# Power_Board.net
KiCad netlist of a schematic drawn in Altium Designer
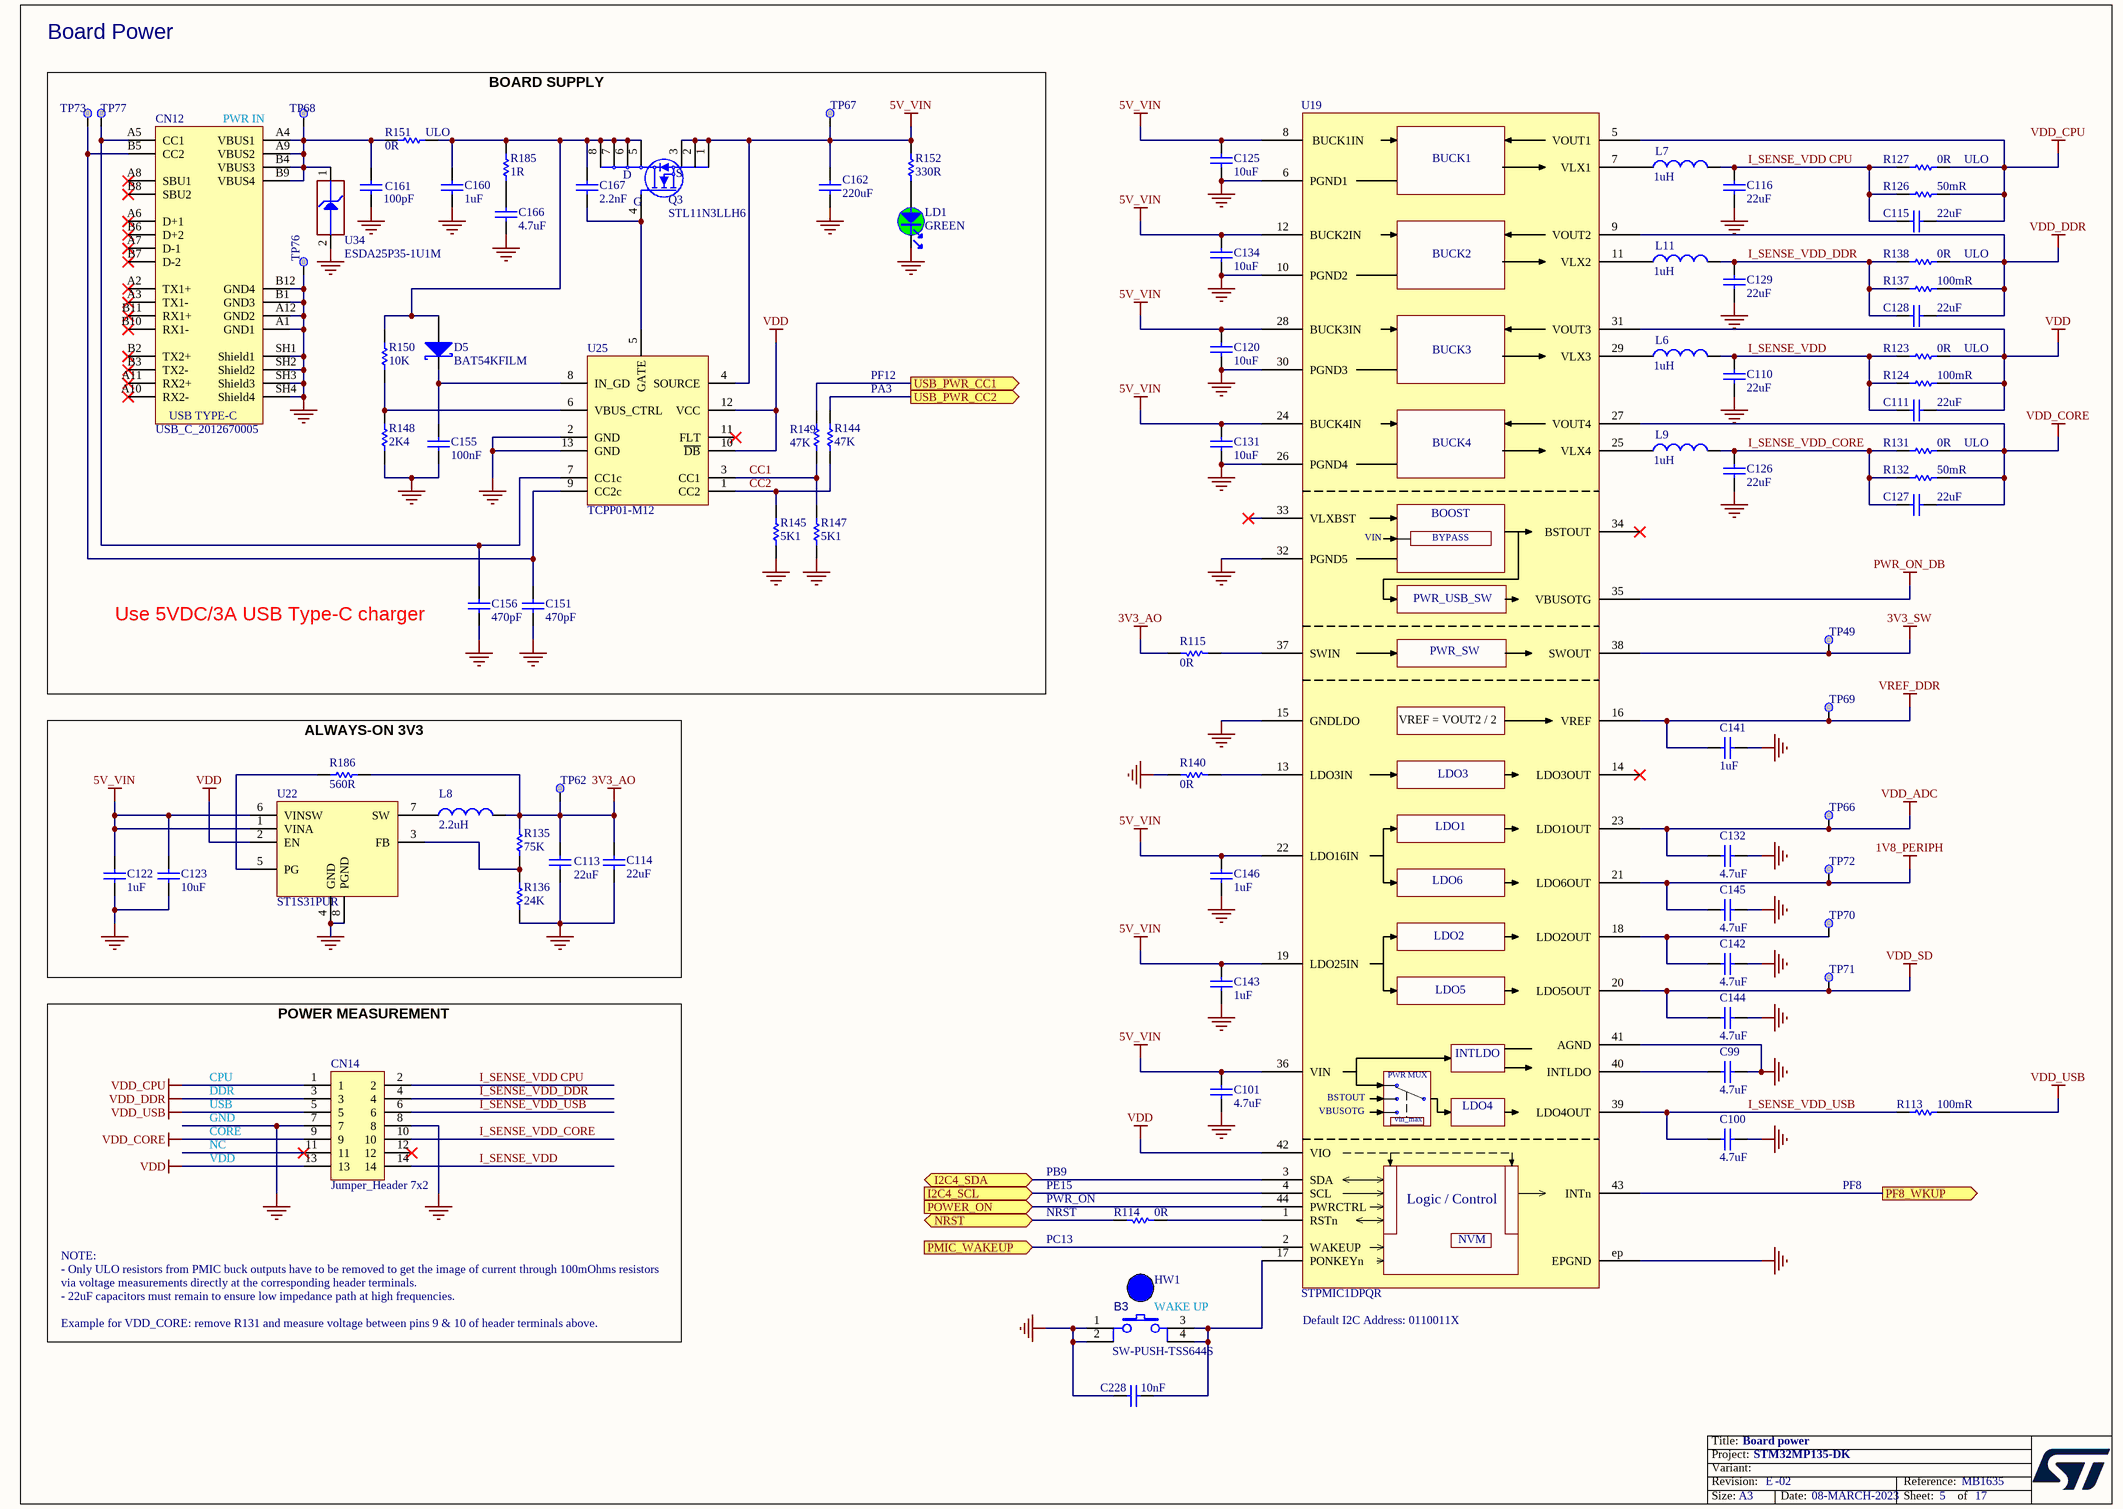
[diagram p0: Power_Board.SchDoc]

(export (version "E")
  (design (tool "Eeschema 10.0.6"))
  (components
    (comp (ref "B3")
      (value "SW-PUSH-TSS644S")
      (footprint "SWI_KNITTER_TSS644S")
      (description "Push Button, NO, 0.05A, 12V, 2.6N, SMD, 9.0x6.2mm, T=7.3mm, changeable caps KTSC-6xx")
      (fields
        (field (name "INTERNAL_PART_NUMBER") "MCD-02417")
        (field (name "MANUFACTURER_PART_NUMBER") "TSS644S")
      )
      (libsource (lib "MCD_PARTS_database") (part "SW_PUSH_SMD"))
    )
    (comp (ref "C99")
      (value "4.7uF")
      (footprint "C0402")
      (description "Capacitor, MLCC, 4.7uF, 6V3, X5R, +/-20%, 0402, T=0.5mm")
      (fields
        (field (name "INTERNAL_PART_NUMBER") "MCD-01356")
        (field (name "MANUFACTURER_PART_NUMBER") "GRM155R60J475ME47")
      )
      (libsource (lib "MCD_PARTS_database") (part "Capacitor"))
    )
    (comp (ref "C100")
      (value "4.7uF")
      (footprint "C0402")
      (description "Capacitor, MLCC, 4.7uF, 6V3, X5R, +/-20%, 0402, T=0.5mm")
      (fields
        (field (name "INTERNAL_PART_NUMBER") "MCD-01356")
        (field (name "MANUFACTURER_PART_NUMBER") "GRM155R60J475ME47")
      )
      (libsource (lib "MCD_PARTS_database") (part "Capacitor"))
    )
    (comp (ref "C101")
      (value "4.7uF")
      (footprint "C0402")
      (description "Capacitor, MLCC, 4.7uF, 6V3, X5R, +/-20%, 0402, T=0.5mm")
      (fields
        (field (name "INTERNAL_PART_NUMBER") "MCD-01356")
        (field (name "MANUFACTURER_PART_NUMBER") "GRM155R60J475ME47")
      )
      (libsource (lib "MCD_PARTS_database") (part "Capacitor"))
    )
    (comp (ref "C110")
      (value "22uF")
      (footprint "C0603")
      (description "Capacitor, MLCC, 22uF, 6V3, X5R, +/-20%, 0603, T=0.8mm")
      (fields
        (field (name "INTERNAL_PART_NUMBER") "MCD-00100")
        (field (name "MANUFACTURER_PART_NUMBER") "GRM188R60J226MEA0J")
      )
      (libsource (lib "MCD_PARTS_database") (part "Capacitor"))
    )
    (comp (ref "C111")
      (value "22uF")
      (footprint "C0603")
      (description "Capacitor, MLCC, 22uF, 6V3, X5R, +/-20%, 0603, T=0.8mm")
      (fields (field (name "INTERNAL_PART_NUMBER") "MCD-00100") (field (name "MANUFACTURER") "MURATA"))
      (libsource (lib "MCD_PARTS_database") (part "Capacitor"))
    )
    (comp (ref "C113")
      (value "22uF")
      (footprint "C0603")
      (description "Capacitor, MLCC, 22uF, 6V3, X5R, +/-20%, 0603, T=0.8mm")
      (fields (field (name "INTERNAL_PART_NUMBER") "MCD-00100") (field (name "MANUFACTURER") "MURATA"))
      (libsource (lib "MCD_PARTS_database") (part "Capacitor"))
    )
    (comp (ref "C114")
      (value "22uF")
      (footprint "C0603")
      (description "Capacitor, MLCC, 22uF, 6V3, X5R, +/-20%, 0603, T=0.8mm")
      (fields (field (name "INTERNAL_PART_NUMBER") "MCD-00100") (field (name "MANUFACTURER") "MURATA"))
      (libsource (lib "MCD_PARTS_database") (part "Capacitor"))
    )
    (comp (ref "C115")
      (value "22uF")
      (footprint "C0603")
      (description "Capacitor, MLCC, 22uF, 6V3, X5R, +/-20%, 0603, T=0.8mm")
      (fields (field (name "INTERNAL_PART_NUMBER") "MCD-00100") (field (name "MANUFACTURER") "MURATA"))
      (libsource (lib "MCD_PARTS_database") (part "Capacitor"))
    )
    (comp (ref "C116")
      (value "22uF")
      (footprint "C0603")
      (description "Capacitor, MLCC, 22uF, 6V3, X5R, +/-20%, 0603, T=0.8mm")
      (fields
        (field (name "INTERNAL_PART_NUMBER") "MCD-00100")
        (field (name "MANUFACTURER_PART_NUMBER") "GRM188R60J226MEA0J")
      )
      (libsource (lib "MCD_PARTS_database") (part "Capacitor"))
    )
    (comp (ref "C120")
      (value "10uF")
      (footprint "C0603")
      (description "Capacitor, MLCC, 10uF, 10V, X5R, +/-10%, 0603, T=0.8mm")
      (fields
        (field (name "INTERNAL_PART_NUMBER") "MCD-00099")
        (field (name "MANUFACTURER_PART_NUMBER") "GRM188R61A106KE69D")
      )
      (libsource (lib "MCD_PARTS_database") (part "Capacitor"))
    )
    (comp (ref "C122")
      (value "1uF")
      (footprint "C0402")
      (description "Capacitor, MLCC, 1uF, 25V, X5R, +/-10%, 0402, T=0.5mm")
      (fields (field (name "INTERNAL_PART_NUMBER") "MCD-00095") (field (name "MANUFACTURER") "MURATA"))
      (libsource (lib "MCD_PARTS_database") (part "Capacitor"))
    )
    (comp (ref "C123")
      (value "10uF")
      (footprint "C0603")
      (description "Capacitor, MLCC, 10uF, 10V, X5R, +/-10%, 0603, T=0.8mm")
      (fields (field (name "INTERNAL_PART_NUMBER") "MCD-00099") (field (name "MANUFACTURER") "MURATA"))
      (libsource (lib "MCD_PARTS_database") (part "Capacitor"))
    )
    (comp (ref "C125")
      (value "10uF")
      (footprint "C0603")
      (description "Capacitor, MLCC, 10uF, 10V, X5R, +/-10%, 0603, T=0.8mm")
      (fields
        (field (name "INTERNAL_PART_NUMBER") "MCD-00099")
        (field (name "MANUFACTURER_PART_NUMBER") "GRM188R61A106KE69D")
      )
      (libsource (lib "MCD_PARTS_database") (part "Capacitor"))
    )
    (comp (ref "C126")
      (value "22uF")
      (footprint "C0603")
      (description "Capacitor, MLCC, 22uF, 6V3, X5R, +/-20%, 0603, T=0.8mm")
      (fields
        (field (name "INTERNAL_PART_NUMBER") "MCD-00100")
        (field (name "MANUFACTURER_PART_NUMBER") "GRM188R60J226MEA0J")
      )
      (libsource (lib "MCD_PARTS_database") (part "Capacitor"))
    )
    (comp (ref "C127")
      (value "22uF")
      (footprint "C0603")
      (description "Capacitor, MLCC, 22uF, 6V3, X5R, +/-20%, 0603, T=0.8mm")
      (fields (field (name "INTERNAL_PART_NUMBER") "MCD-00100") (field (name "MANUFACTURER") "MURATA"))
      (libsource (lib "MCD_PARTS_database") (part "Capacitor"))
    )
    (comp (ref "C128")
      (value "22uF")
      (footprint "C0603")
      (description "Capacitor, MLCC, 22uF, 6V3, X5R, +/-20%, 0603, T=0.8mm")
      (fields (field (name "INTERNAL_PART_NUMBER") "MCD-00100") (field (name "MANUFACTURER") "MURATA"))
      (libsource (lib "MCD_PARTS_database") (part "Capacitor"))
    )
    (comp (ref "C129")
      (value "22uF")
      (footprint "C0603")
      (description "Capacitor, MLCC, 22uF, 6V3, X5R, +/-20%, 0603, T=0.8mm")
      (fields
        (field (name "INTERNAL_PART_NUMBER") "MCD-00100")
        (field (name "MANUFACTURER_PART_NUMBER") "GRM188R60J226MEA0J")
      )
      (libsource (lib "MCD_PARTS_database") (part "Capacitor"))
    )
    (comp (ref "C131")
      (value "10uF")
      (footprint "C0603")
      (description "Capacitor, MLCC, 10uF, 10V, X5R, +/-10%, 0603, T=0.8mm")
      (fields
        (field (name "INTERNAL_PART_NUMBER") "MCD-00099")
        (field (name "MANUFACTURER_PART_NUMBER") "GRM188R61A106KE69D")
      )
      (libsource (lib "MCD_PARTS_database") (part "Capacitor"))
    )
    (comp (ref "C132")
      (value "4.7uF")
      (footprint "C0402")
      (description "Capacitor, MLCC, 4.7uF, 6V3, X5R, +/-20%, 0402, T=0.5mm")
      (fields
        (field (name "INTERNAL_PART_NUMBER") "MCD-01356")
        (field (name "MANUFACTURER_PART_NUMBER") "GRM155R60J475ME47")
      )
      (libsource (lib "MCD_PARTS_database") (part "Capacitor"))
    )
    (comp (ref "C134")
      (value "10uF")
      (footprint "C0603")
      (description "Capacitor, MLCC, 10uF, 10V, X5R, +/-10%, 0603, T=0.8mm")
      (fields
        (field (name "INTERNAL_PART_NUMBER") "MCD-00099")
        (field (name "MANUFACTURER_PART_NUMBER") "GRM188R61A106KE69D")
      )
      (libsource (lib "MCD_PARTS_database") (part "Capacitor"))
    )
    (comp (ref "C141")
      (value "1uF")
      (footprint "C0402")
      (description "Capacitor, MLCC, 1uF, 25V, X5R, +/-10%, 0402, T=0.5mm")
      (fields
        (field (name "INTERNAL_PART_NUMBER") "MCD-00095")
        (field (name "MANUFACTURER_PART_NUMBER") "GRM155R61E105KA12")
      )
      (libsource (lib "MCD_PARTS_database") (part "Capacitor"))
    )
    (comp (ref "C142")
      (value "4.7uF")
      (footprint "C0402")
      (description "Capacitor, MLCC, 4.7uF, 6V3, X5R, +/-20%, 0402, T=0.5mm")
      (fields
        (field (name "INTERNAL_PART_NUMBER") "MCD-01356")
        (field (name "MANUFACTURER_PART_NUMBER") "GRM155R60J475ME47")
      )
      (libsource (lib "MCD_PARTS_database") (part "Capacitor"))
    )
    (comp (ref "C143")
      (value "1uF")
      (footprint "C0402")
      (description "Capacitor, MLCC, 1uF, 25V, X5R, +/-10%, 0402, T=0.5mm")
      (fields
        (field (name "INTERNAL_PART_NUMBER") "MCD-00095")
        (field (name "MANUFACTURER_PART_NUMBER") "GRM155R61E105KA12")
      )
      (libsource (lib "MCD_PARTS_database") (part "Capacitor"))
    )
    (comp (ref "C144")
      (value "4.7uF")
      (footprint "C0402")
      (description "Capacitor, MLCC, 4.7uF, 6V3, X5R, +/-20%, 0402, T=0.5mm")
      (fields
        (field (name "INTERNAL_PART_NUMBER") "MCD-01356")
        (field (name "MANUFACTURER_PART_NUMBER") "GRM155R60J475ME47")
      )
      (libsource (lib "MCD_PARTS_database") (part "Capacitor"))
    )
    (comp (ref "C145")
      (value "4.7uF")
      (footprint "C0402")
      (description "Capacitor, MLCC, 4.7uF, 6V3, X5R, +/-20%, 0402, T=0.5mm")
      (fields
        (field (name "INTERNAL_PART_NUMBER") "MCD-01356")
        (field (name "MANUFACTURER_PART_NUMBER") "GRM155R60J475ME47")
      )
      (libsource (lib "MCD_PARTS_database") (part "Capacitor"))
    )
    (comp (ref "C146")
      (value "1uF")
      (footprint "C0402")
      (description "Capacitor, MLCC, 1uF, 25V, X5R, +/-10%, 0402, T=0.5mm")
      (fields
        (field (name "INTERNAL_PART_NUMBER") "MCD-00095")
        (field (name "MANUFACTURER_PART_NUMBER") "GRM155R61E105KA12")
      )
      (libsource (lib "MCD_PARTS_database") (part "Capacitor"))
    )
    (comp (ref "C151")
      (value "470pF")
      (footprint "C0402")
      (description "Capacitor, MLCC, 470pF, 50V, NPO, +/-5%, 0402, T=0.5mm")
      (fields
        (field (name "INTERNAL_PART_NUMBER") "MCD-00724")
        (field (name "MANUFACTURER_PART_NUMBER") "CC0402JRNPO9BN471")
      )
      (libsource (lib "MCD_PARTS_database") (part "Capacitor"))
    )
    (comp (ref "C155")
      (value "100nF")
      (footprint "C0603")
      (description "Capacitor, MLCC, 100nF, 50V, X7R, +/-10%, 0603, T=0.8mm")
      (fields
        (field (name "INTERNAL_PART_NUMBER") "MCD-01099")
        (field (name "MANUFACTURER_PART_NUMBER") "CC0603KRX7R9BB104")
      )
      (libsource (lib "MCD_PARTS_database") (part "Capacitor"))
    )
    (comp (ref "C156")
      (value "470pF")
      (footprint "C0402")
      (description "Capacitor, MLCC, 470pF, 50V, NPO, +/-5%, 0402, T=0.5mm")
      (fields
        (field (name "INTERNAL_PART_NUMBER") "MCD-00724")
        (field (name "MANUFACTURER_PART_NUMBER") "CC0402JRNPO9BN471")
      )
      (libsource (lib "MCD_PARTS_database") (part "Capacitor"))
    )
    (comp (ref "C160")
      (value "1uF")
      (footprint "C0402")
      (description "Capacitor, MLCC, 1uF, 25V, X5R, +/-10%, 0402, T=0.5mm")
      (fields
        (field (name "INTERNAL_PART_NUMBER") "MCD-00095")
        (field (name "MANUFACTURER_PART_NUMBER") "GRM155R61E105KA12")
      )
      (libsource (lib "MCD_PARTS_database") (part "Capacitor"))
    )
    (comp (ref "C161")
      (value "100pF")
      (footprint "C0402")
      (description "Capacitor, MLCC, 100pF, 50V, NPO, +/-5%, 0402, T=0.5mm")
      (fields
        (field (name "INTERNAL_PART_NUMBER") "MCD-00205")
        (field (name "MANUFACTURER_PART_NUMBER") "CC0402JRNPO9BN101")
      )
      (libsource (lib "MCD_PARTS_database") (part "Capacitor"))
    )
    (comp (ref "C162")
      (value "220uF")
      (footprint "C1206_H1P6")
      (description "Capacitor, MLCC, 220uF, 6V3, X5R, +/-20%, 1206, T=1.6mm")
      (fields
        (field (name "INTERNAL_PART_NUMBER") "MCD-00104")
        (field (name "MANUFACTURER_PART_NUMBER") "GRM31CR60J227ME11")
      )
      (libsource (lib "MCD_PARTS_database") (part "Capacitor"))
    )
    (comp (ref "C166")
      (value "4.7uF")
      (footprint "C0603")
      (description "Capacitor, MLCC, 4.7uF, 25V, X5R, +/-10%, 0603, T=0.8mm")
      (fields
        (field (name "INTERNAL_PART_NUMBER") "MCD-02196")
        (field (name "MANUFACTURER_PART_NUMBER") "C1608X5R1E475K080AC")
      )
      (libsource (lib "MCD_PARTS_database") (part "Capacitor"))
    )
    (comp (ref "C167")
      (value "2.2nF")
      (footprint "C0603_H0P8")
      (description "Capacitor, MLCC, 2.2nF, 50V, C0G/NPO, +/-5%, 0603, T=0,8mm")
      (fields (field (name "INTERNAL_PART_NUMBER") "MCD-02457") (field (name "MANUFACTURER") "YAGEO"))
      (libsource (lib "MCD_PARTS_database") (part "Capacitor"))
    )
    (comp (ref "C228")
      (value "10nF")
      (footprint "C0402")
      (description "Capacitor, MLCC, 10nF, 50V, X7R, +/-10%, 0402, T=0.5mm")
      (fields
        (field (name "INTERNAL_PART_NUMBER") "MCD-02198")
        (field (name "MANUFACTURER_PART_NUMBER") "CC0402KRX7R9BB103")
      )
      (libsource (lib "MCD_PARTS_database") (part "Capacitor"))
    )
    (comp (ref "CN12")
      (value "USB_C_2012670005")
      (footprint "CON_USB-TYPEC_MOLEX_2012670005")
      (description "USB_TypeC, 24 pins, RA, SMD, T=3.71mm (USB Certified 3.1)")
      (fields
        (field (name "INTERNAL_PART_NUMBER") "MCD-02421")
        (field (name "MANUFACTURER_PART_NUMBER") "2012670005")
      )
      (libsource (lib "MCD_PARTS_database") (part "USB_TYPE_C_Receptacle"))
    )
    (comp (ref "CN14")
      (value "Jumper_Header 7x2")
      (footprint "CON_SAMTEC_TSW-107-07-X-D")
      (description "Header, 7x2, 2.54mm, VR, TH, T=5.84mm/2.54mm")
      (fields (field (name "INTERNAL_PART_NUMBER") "MCD-02123") (field (name "MANUFACTURER") "SAMTEC"))
      (libsource (lib "MCD_PARTS_database") (part "Header 7x2"))
    )
    (comp (ref "D5")
      (value "BAT54KFILM")
      (footprint "DIO_SOD523_1A_2K")
      (description "Small signal Schottky diodes")
      (fields (field (name "INTERNAL_PART_NUMBER") "MCD-01677") (field (name "BMS_PART_NUMBER") "9151123"))
      (libsource (lib "MCD_PARTS_database") (part "SCHOTTKY_1A_2K"))
    )
    (comp (ref "HW1")
      (value "Blue Hat")
      (description "Switch hat, blue, For KTSC-62B")
      (fields (field (name "INTERNAL_PART_NUMBER") "MCD-02136") (field (name "MANUFACTURER") "APEM INC"))
      (libsource (lib "MCD_PARTS_database") (part "BUTTON_HAT_BLUE"))
    )
    (comp (ref "L6")
      (value "1uH")
      (footprint "IND_2520_TOKO_DFE252012P")
      (description "Inductor, 1uH, +/-20%, 4.3A max, 0R042, 2520, T=1.2mm")
      (fields
        (field (name "INTERNAL_PART_NUMBER") "MCD-01122")
        (field (name "MANUFACTURER_PART_NUMBER") "DFE252012P-1ROM=P2")
      )
      (libsource (lib "MCD_PARTS_database") (part "IND_1uH_42mohm_3.2A"))
    )
    (comp (ref "L7")
      (value "1uH")
      (footprint "IND_2520_TOKO_DFE252012P")
      (description "Inductor, 1uH, +/-20%, 4.3A max, 0R042, 2520, T=1.2mm")
      (fields
        (field (name "INTERNAL_PART_NUMBER") "MCD-01122")
        (field (name "MANUFACTURER_PART_NUMBER") "DFE252012P-1ROM=P2")
      )
      (libsource (lib "MCD_PARTS_database") (part "IND_1uH_42mohm_3.2A"))
    )
    (comp (ref "L8")
      (value "2.2uH")
      (footprint "IND_4025_WURTH_74404043022A")
      (description "Inductor, 2.2uH, +/-30%, 3,83A, 0R023, 4x4mm, T=2.5mm")
      (fields
        (field (name "INTERNAL_PART_NUMBER") "MCD-02242")
        (field (name "MANUFACTURER") "WURTH ELEKTRONIK")
      )
      (libsource (lib "MCD_PARTS_database") (part "Inductor"))
    )
    (comp (ref "L9")
      (value "1uH")
      (footprint "IND_2520_TOKO_DFE252012P")
      (description "Inductor, 1uH, +/-20%, 4.3A max, 0R042, 2520, T=1.2mm")
      (fields
        (field (name "INTERNAL_PART_NUMBER") "MCD-01122")
        (field (name "MANUFACTURER_PART_NUMBER") "DFE252012P-1ROM=P2")
      )
      (libsource (lib "MCD_PARTS_database") (part "IND_1uH_42mohm_3.2A"))
    )
    (comp (ref "L11")
      (value "1uH")
      (footprint "IND_2520_TOKO_DFE252012P")
      (description "Inductor, 1uH, +/-20%, 4.3A max, 0R042, 2520, T=1.2mm")
      (fields
        (field (name "INTERNAL_PART_NUMBER") "MCD-01122")
        (field (name "MANUFACTURER_PART_NUMBER") "DFE252012P-1ROM=P2")
      )
      (libsource (lib "MCD_PARTS_database") (part "IND_1uH_42mohm_3.2A"))
    )
    (comp (ref "LD1")
      (value "GREEN")
      (footprint "LED_0603_GREEN")
      (description "LED, Green, 0603")
      (fields
        (field (name "INTERNAL_PART_NUMBER") "MCD-00050")
        (field (name "MANUFACTURER_PART_NUMBER") "19-213SYGC/S530-E2/TR8")
      )
      (libsource (lib "MCD_PARTS_database") (part "LED_green"))
    )
    (comp (ref "Q3")
      (value "STL11N3LLH6")
      (footprint "MOS_POWERFLAT_3P3X3P3_P065")
      (description "N-channel 30 V, 6 mΩ typ, 11 A STripFET™ H6, Power MOSFET in a PowerFLAT™ 3.3x3.3 package")
      (fields
        (field (name "INTERNAL_PART_NUMBER") "MCD-01810")
        (field (name "MANUFACTURER") "STMICROELECTRONICS")
      )
      (libsource (lib "MCD_PARTS_database") (part "STL11N3LLH6"))
    )
    (comp (ref "R113")
      (value "100mR")
      (footprint "R0603")
      (description "Resistor, 100mR, 0603, +/- 1%, 1/3W")
      (fields (field (name "INTERNAL_PART_NUMBER") "MCD-02234") (field (name "MANUFACTURER") "PANASONIC"))
      (libsource (lib "MCD_PARTS_database") (part "Resistor"))
    )
    (comp (ref "R114")
      (value "0R")
      (footprint "R0402")
      (description "Resistor, 0R, 0402, +/-5%, 1/16W")
      (fields
        (field (name "INTERNAL_PART_NUMBER") "MCD-00052")
        (field (name "MANUFACTURER_PART_NUMBER") "RC0402JR-070RL")
      )
      (libsource (lib "MCD_PARTS_database") (part "Resistor"))
    )
    (comp (ref "R115")
      (value "0R")
      (footprint "R0402")
      (description "Resistor, 0R, 0402, +/-5%, 1/16W")
      (fields
        (field (name "INTERNAL_PART_NUMBER") "MCD-00052")
        (field (name "MANUFACTURER_PART_NUMBER") "RC0402JR-070RL")
      )
      (libsource (lib "MCD_PARTS_database") (part "Resistor"))
    )
    (comp (ref "R123")
      (value "0R")
      (footprint "R0603")
      (description "Resistor, 0R, 0603, +/- 0.5mR, 1/4W")
      (fields (field (name "INTERNAL_PART_NUMBER") "MCD-00181") (field (name "MANUFACTURER") "ROHM"))
      (libsource (lib "MCD_PARTS_database") (part "Resistor"))
    )
    (comp (ref "R124")
      (value "100mR")
      (footprint "R0603")
      (description "Resistor, 100mR, 0603, +/- 1%, 1/3W")
      (fields (field (name "INTERNAL_PART_NUMBER") "MCD-02234") (field (name "MANUFACTURER") "PANASONIC"))
      (libsource (lib "MCD_PARTS_database") (part "Resistor"))
    )
    (comp (ref "R126")
      (value "50mR")
      (footprint "R0603")
      (description "Resistor, 50mR, 0603, +/-1%, 1/3W")
      (fields (field (name "INTERNAL_PART_NUMBER") "MCD-02233") (field (name "MANUFACTURER") "PANASONIC"))
      (libsource (lib "MCD_PARTS_database") (part "Resistor"))
    )
    (comp (ref "R127")
      (value "0R")
      (footprint "R0603")
      (description "Resistor, 0R, 0603, +/- 0.5mR, 1/4W")
      (fields (field (name "INTERNAL_PART_NUMBER") "MCD-00181") (field (name "MANUFACTURER") "ROHM"))
      (libsource (lib "MCD_PARTS_database") (part "Resistor"))
    )
    (comp (ref "R131")
      (value "0R")
      (footprint "R0603")
      (description "Resistor, 0R, 0603, +/- 0.5mR, 1/4W")
      (fields (field (name "INTERNAL_PART_NUMBER") "MCD-00181") (field (name "MANUFACTURER") "ROHM"))
      (libsource (lib "MCD_PARTS_database") (part "Resistor"))
    )
    (comp (ref "R132")
      (value "50mR")
      (footprint "R0603")
      (description "Resistor, 50mR, 0603, +/-1%, 1/3W")
      (fields (field (name "INTERNAL_PART_NUMBER") "MCD-02233") (field (name "MANUFACTURER") "PANASONIC"))
      (libsource (lib "MCD_PARTS_database") (part "Resistor"))
    )
    (comp (ref "R135")
      (value "75K")
      (footprint "R0402")
      (description "Resistor, 75K, 0402, +/-1%, 1/16W")
      (fields (field (name "INTERNAL_PART_NUMBER") "MCD-00521") (field (name "MANUFACTURER") "YAGEO"))
      (libsource (lib "MCD_PARTS_database") (part "Resistor"))
    )
    (comp (ref "R136")
      (value "24K")
      (footprint "R0402")
      (description "Resistor, 24K, 0402, +/-1%, 1/16W")
      (fields (field (name "INTERNAL_PART_NUMBER") "MCD-00435") (field (name "MANUFACTURER") "YAGEO"))
      (libsource (lib "MCD_PARTS_database") (part "Resistor"))
    )
    (comp (ref "R137")
      (value "100mR")
      (footprint "R0603")
      (description "Resistor, 100mR, 0603, +/- 1%, 1/3W")
      (fields (field (name "INTERNAL_PART_NUMBER") "MCD-02234") (field (name "MANUFACTURER") "PANASONIC"))
      (libsource (lib "MCD_PARTS_database") (part "Resistor"))
    )
    (comp (ref "R138")
      (value "0R")
      (footprint "R0603")
      (description "Resistor, 0R, 0603, +/- 0.5mR, 1/4W")
      (fields (field (name "INTERNAL_PART_NUMBER") "MCD-00181") (field (name "MANUFACTURER") "ROHM"))
      (libsource (lib "MCD_PARTS_database") (part "Resistor"))
    )
    (comp (ref "R140")
      (value "0R")
      (footprint "R0402")
      (description "Resistor, 0R, 0402, +/-5%, 1/16W")
      (fields
        (field (name "INTERNAL_PART_NUMBER") "MCD-00052")
        (field (name "MANUFACTURER_PART_NUMBER") "RC0402JR-070RL")
      )
      (libsource (lib "MCD_PARTS_database") (part "Resistor"))
    )
    (comp (ref "R144")
      (value "47K")
      (footprint "R0402")
      (description "Resistor, 47K, 0402, +/-1%, 1/16W")
      (fields
        (field (name "INTERNAL_PART_NUMBER") "MCD-00063")
        (field (name "MANUFACTURER_PART_NUMBER") "RC0402FR-0747KL")
      )
      (libsource (lib "MCD_PARTS_database") (part "Resistor"))
    )
    (comp (ref "R145")
      (value "5K1")
      (footprint "R0402")
      (description "Resistor, 5K1, 0402, +/-1%, 1/16W")
      (fields
        (field (name "INTERNAL_PART_NUMBER") "MCD-00333")
        (field (name "MANUFACTURER_PART_NUMBER") "RC0402FR-075K1L")
      )
      (libsource (lib "MCD_PARTS_database") (part "Resistor"))
    )
    (comp (ref "R147")
      (value "5K1")
      (footprint "R0402")
      (description "Resistor, 5K1, 0402, +/-1%, 1/16W")
      (fields
        (field (name "INTERNAL_PART_NUMBER") "MCD-00333")
        (field (name "MANUFACTURER_PART_NUMBER") "RC0402FR-075K1L")
      )
      (libsource (lib "MCD_PARTS_database") (part "Resistor"))
    )
    (comp (ref "R148")
      (value "2K4")
      (footprint "R0402")
      (description "Resistor, 2K4, 0402, +/-1%, 1/16W")
      (fields (field (name "INTERNAL_PART_NUMBER") "MCD-00433") (field (name "MANUFACTURER") "YAGEO"))
      (libsource (lib "MCD_PARTS_database") (part "Resistor"))
    )
    (comp (ref "R149")
      (value "47K")
      (footprint "R0402")
      (description "Resistor, 47K, 0402, +/-1%, 1/16W")
      (fields
        (field (name "INTERNAL_PART_NUMBER") "MCD-00063")
        (field (name "MANUFACTURER_PART_NUMBER") "RC0402FR-0747KL")
      )
      (libsource (lib "MCD_PARTS_database") (part "Resistor"))
    )
    (comp (ref "R150")
      (value "10K")
      (footprint "R0402")
      (description "Resistor, 10K, 0402, +/-1%, 1/16W")
      (fields (field (name "INTERNAL_PART_NUMBER") "MCD-00053") (field (name "BMS_PART_NUMBER") "9131590"))
      (libsource (lib "MCD_PARTS_database") (part "Resistor"))
    )
    (comp (ref "R151")
      (value "0R")
      (footprint "R0603")
      (description "Resistor, 0R, 0603, +/- 0.5mR, 1/4W")
      (fields
        (field (name "INTERNAL_PART_NUMBER") "MCD-00181")
        (field (name "MANUFACTURER_PART_NUMBER") "PMR03EZPJ000")
      )
      (libsource (lib "MCD_PARTS_database") (part "Resistor"))
    )
    (comp (ref "R152")
      (value "330R")
      (footprint "R0402")
      (description "Resistor, 330R, 0402, +/-1%, 1/16W")
      (fields
        (field (name "INTERNAL_PART_NUMBER") "MCD-00062")
        (field (name "MANUFACTURER_PART_NUMBER") "RC0402FR-07330RL")
      )
      (libsource (lib "MCD_PARTS_database") (part "Resistor"))
    )
    (comp (ref "R185")
      (value "1R")
      (footprint "R0603")
      (description "Resistor, 1R, 0603, +/-1%, 1/10W")
      (fields (field (name "INTERNAL_PART_NUMBER") "MCD-01512") (field (name "MANUFACTURER") "YAGEO"))
      (libsource (lib "MCD_PARTS_database") (part "Resistor"))
    )
    (comp (ref "R186")
      (value "560R")
      (footprint "R0402")
      (description "Resistor, 560R, 0402, +/-1%, 1/16W")
      (fields (field (name "INTERNAL_PART_NUMBER") "MCD-00489") (field (name "MANUFACTURER") "YAGEO"))
      (libsource (lib "MCD_PARTS_database") (part "Resistor"))
    )
    (comp (ref "TP49")
      (value "Test Point")
      (footprint "TP_SMD_1MM")
      (description "Test Point 1mm")
      (fields (field (name "INTERNAL_PART_NUMBER") "MCD-00074"))
      (libsource (lib "MCD_PARTS_database") (part "Test Point"))
    )
    (comp (ref "TP62")
      (value "Test Point")
      (footprint "TP_SMD_1MM")
      (description "Test Point 1mm")
      (fields (field (name "INTERNAL_PART_NUMBER") "MCD-00074"))
      (libsource (lib "MCD_PARTS_database") (part "Test Point"))
    )
    (comp (ref "TP66")
      (value "Test Point")
      (footprint "TP_SMD_1MM")
      (description "Test Point 1mm")
      (fields (field (name "INTERNAL_PART_NUMBER") "MCD-00074"))
      (libsource (lib "MCD_PARTS_database") (part "Test Point"))
    )
    (comp (ref "TP67")
      (value "Test Point")
      (footprint "TP_SMD_1MM")
      (description "Test Point 1mm")
      (fields (field (name "INTERNAL_PART_NUMBER") "MCD-00074"))
      (libsource (lib "MCD_PARTS_database") (part "Test Point"))
    )
    (comp (ref "TP68")
      (value "Test Point")
      (footprint "TP_SMD_2MM")
      (description "Test Point 2mm")
      (fields (field (name "INTERNAL_PART_NUMBER") "MCD-00177"))
      (libsource (lib "MCD_PARTS_database") (part "Test Point"))
    )
    (comp (ref "TP69")
      (value "Test Point")
      (footprint "TP_SMD_1MM")
      (description "Test Point 1mm")
      (fields (field (name "INTERNAL_PART_NUMBER") "MCD-00074"))
      (libsource (lib "MCD_PARTS_database") (part "Test Point"))
    )
    (comp (ref "TP70")
      (value "Test Point")
      (footprint "TP_SMD_1MM")
      (description "Test Point 1mm")
      (fields (field (name "INTERNAL_PART_NUMBER") "MCD-00074"))
      (libsource (lib "MCD_PARTS_database") (part "Test Point"))
    )
    (comp (ref "TP71")
      (value "Test Point")
      (footprint "TP_SMD_1MM")
      (description "Test Point 1mm")
      (fields (field (name "INTERNAL_PART_NUMBER") "MCD-00074"))
      (libsource (lib "MCD_PARTS_database") (part "Test Point"))
    )
    (comp (ref "TP72")
      (value "Test Point")
      (footprint "TP_SMD_1MM")
      (description "Test Point 1mm")
      (fields (field (name "INTERNAL_PART_NUMBER") "MCD-00074"))
      (libsource (lib "MCD_PARTS_database") (part "Test Point"))
    )
    (comp (ref "TP73")
      (value "Test Point")
      (footprint "TP_SMD_1MM")
      (description "Test Point 1mm")
      (fields (field (name "INTERNAL_PART_NUMBER") "MCD-00074"))
      (libsource (lib "MCD_PARTS_database") (part "Test Point"))
    )
    (comp (ref "TP76")
      (value "Test Point")
      (footprint "TP_SMD_2MM")
      (description "Test Point 2mm")
      (fields (field (name "INTERNAL_PART_NUMBER") "MCD-00177"))
      (libsource (lib "MCD_PARTS_database") (part "Test Point"))
    )
    (comp (ref "TP77")
      (value "Test Point")
      (footprint "TP_SMD_1MM")
      (description "Test Point 1mm")
      (fields (field (name "INTERNAL_PART_NUMBER") "MCD-00074"))
      (libsource (lib "MCD_PARTS_database") (part "Test Point"))
    )
    (comp (ref "U19")
      (value "STPMIC1DPQR")
      (footprint "ICC_WFQFN44-EPAD_5X6_P040")
      (fields
        (field (name "INTERNAL_PART_NUMBER") "MCD-02275")
        (field (name "MANUFACTURER") "STMICROELECTRONICS")
        (field (name "Comment") "STPMU1")
      )
      (libsource (lib "MCD_PARTS_database") (part "STPMU1"))
    )
    (comp (ref "U22")
      (value "ST1S31PUR")
      (footprint "ICC_VFDFPN8-EPAD_3X3_P065")
      (description "3A DC step-down switching regulator 1,5MHz")
      (fields
        (field (name "INTERNAL_PART_NUMBER") "MCD-02243")
        (field (name "MANUFACTURER") "STMICROELECTRONICS")
      )
      (libsource (lib "MCD_PARTS_database") (part "ST1S31PUR"))
    )
    (comp (ref "U25")
      (value "TCPP01-M12")
      (footprint "ICC_QFN12L-EPAD_3X3_P050")
      (description "USB Type-C Port Protection for USB Power Delivery, PPS compliant")
      (fields (field (name "INTERNAL_PART_NUMBER") "MCD-01809") (field (name "BMS_PART_NUMBER") "9151145"))
      (libsource (lib "MCD_PARTS_database") (part "TCPP01-M12"))
    )
    (comp (ref "U34")
      (value "ESDA25P35-1U1M")
      (footprint "ESD_QFN1610_2N_1K_2A")
      (description "High power Transient voltage suppressor:25V/35A EOS and ESD transients protection.")
      (fields (field (name "INTERNAL_PART_NUMBER") "MCD-01207") (field (name "BMS_PART_NUMBER") "9179045"))
      (libsource (lib "MCD_PARTS_database") (part "ESD-TRANSIL"))
    )
  )
  (nets
    (net (code "1") (name "/CC1") (class "Default")
      (node (ref "R147") (pin "2") (pinfunction "2_2") (pintype "passive"))
      (node (ref "R149") (pin "1") (pinfunction "1_1") (pintype "passive"))
      (node (ref "U25") (pin "3") (pinfunction "CC1_3") (pintype "passive"))
    )
    (net (code "2") (name "/CC2") (class "Default")
      (node (ref "R144") (pin "1") (pinfunction "1_1") (pintype "passive"))
      (node (ref "R145") (pin "2") (pinfunction "2_2") (pintype "passive"))
      (node (ref "U25") (pin "1") (pinfunction "CC2_1") (pintype "passive"))
    )
    (net (code "3") (name "/I2C4_SCL") (class "Default")
      (node (ref "U19") (pin "4") (pinfunction "SCL_4") (pintype "passive"))
    )
    (net (code "4") (name "/I2C4_SDA") (class "Default")
      (node (ref "U19") (pin "3") (pinfunction "SDA_3") (pintype "passive"))
    )
    (net (code "5") (name "/I_SENSE_VDD") (class "Default")
      (node (ref "C110") (pin "2") (pinfunction "2_2") (pintype "passive"))
      (node (ref "C111") (pin "1") (pinfunction "1_1") (pintype "passive"))
      (node (ref "CN14") (pin "14") (pinfunction "14_14") (pintype "passive"))
      (node (ref "L6") (pin "2") (pinfunction "2_2") (pintype "passive"))
      (node (ref "R123") (pin "1") (pinfunction "1_1") (pintype "passive"))
      (node (ref "R124") (pin "1") (pinfunction "1_1") (pintype "passive"))
    )
    (net (code "6") (name "/I_SENSE_VDD CPU") (class "Default")
      (node (ref "C115") (pin "1") (pinfunction "1_1") (pintype "passive"))
      (node (ref "C116") (pin "2") (pinfunction "2_2") (pintype "passive"))
      (node (ref "CN14") (pin "2") (pinfunction "2_2") (pintype "passive"))
      (node (ref "L7") (pin "2") (pinfunction "2_2") (pintype "passive"))
      (node (ref "R126") (pin "1") (pinfunction "1_1") (pintype "passive"))
      (node (ref "R127") (pin "1") (pinfunction "1_1") (pintype "passive"))
    )
    (net (code "7") (name "/I_SENSE_VDD_CORE") (class "Default")
      (node (ref "C126") (pin "2") (pinfunction "2_2") (pintype "passive"))
      (node (ref "C127") (pin "1") (pinfunction "1_1") (pintype "passive"))
      (node (ref "CN14") (pin "10") (pinfunction "10_10") (pintype "passive"))
      (node (ref "L9") (pin "2") (pinfunction "2_2") (pintype "passive"))
      (node (ref "R131") (pin "1") (pinfunction "1_1") (pintype "passive"))
      (node (ref "R132") (pin "1") (pinfunction "1_1") (pintype "passive"))
    )
    (net (code "8") (name "/I_SENSE_VDD_DDR") (class "Default")
      (node (ref "C128") (pin "1") (pinfunction "1_1") (pintype "passive"))
      (node (ref "C129") (pin "2") (pinfunction "2_2") (pintype "passive"))
      (node (ref "CN14") (pin "4") (pinfunction "4_4") (pintype "passive"))
      (node (ref "L11") (pin "2") (pinfunction "2_2") (pintype "passive"))
      (node (ref "R137") (pin "1") (pinfunction "1_1") (pintype "passive"))
      (node (ref "R138") (pin "1") (pinfunction "1_1") (pintype "passive"))
    )
    (net (code "9") (name "/I_SENSE_VDD_USB") (class "Default")
      (node (ref "C100") (pin "2") (pinfunction "2_2") (pintype "passive"))
      (node (ref "CN14") (pin "6") (pinfunction "6_6") (pintype "passive"))
      (node (ref "R113") (pin "1") (pinfunction "1_1") (pintype "passive"))
      (node (ref "U19") (pin "39") (pinfunction "LDO4OUT_39") (pintype "passive"))
    )
    (net (code "10") (name "/NRST") (class "Default")
      (node (ref "R114") (pin "1") (pinfunction "1_1") (pintype "passive"))
    )
    (net (code "11") (name "/PF8_WKUP") (class "Default")
      (node (ref "U19") (pin "43") (pinfunction "INTn_43") (pintype "passive"))
    )
    (net (code "12") (name "/PMIC_WAKEUP") (class "Default")
      (node (ref "U19") (pin "2") (pinfunction "WAKEUP_2") (pintype "passive"))
    )
    (net (code "13") (name "/POWER_ON") (class "Default")
      (node (ref "U19") (pin "44") (pinfunction "PWRCTRL_44") (pintype "passive"))
    )
    (net (code "14") (name "/USB_PWR_CC1") (class "Default")
      (node (ref "R149") (pin "2") (pinfunction "2_2") (pintype "passive"))
    )
    (net (code "15") (name "/USB_PWR_CC2") (class "Default")
      (node (ref "R144") (pin "2") (pinfunction "2_2") (pintype "passive"))
    )
    (net (code "16") (name "1V8_PERIPH") (class "Default")
      (node (ref "C145") (pin "2") (pinfunction "2_2") (pintype "passive"))
      (node (ref "TP72") (pin "1") (pinfunction "1_1") (pintype "passive"))
      (node (ref "U19") (pin "21") (pinfunction "LDO6OUT_21") (pintype "passive"))
    )
    (net (code "17") (name "3V3_AO") (class "Default")
      (node (ref "C113") (pin "2") (pinfunction "2_2") (pintype "passive"))
      (node (ref "C114") (pin "2") (pinfunction "2_2") (pintype "passive"))
      (node (ref "L8") (pin "2") (pinfunction "2_2") (pintype "passive"))
      (node (ref "R115") (pin "1") (pinfunction "1_1") (pintype "passive"))
      (node (ref "R135") (pin "2") (pinfunction "2_2") (pintype "passive"))
      (node (ref "R186") (pin "2") (pinfunction "2_2") (pintype "passive"))
      (node (ref "TP62") (pin "1") (pinfunction "1_1") (pintype "passive"))
    )
    (net (code "18") (name "3V3_SW") (class "Default")
      (node (ref "TP49") (pin "1") (pinfunction "1_1") (pintype "passive"))
      (node (ref "U19") (pin "38") (pinfunction "SWOUT_38") (pintype "passive"))
    )
    (net (code "19") (name "5V_VIN") (class "Default")
      (node (ref "C101") (pin "2") (pinfunction "2_2") (pintype "passive"))
      (node (ref "C120") (pin "2") (pinfunction "2_2") (pintype "passive"))
      (node (ref "C122") (pin "2") (pinfunction "2_2") (pintype "passive"))
      (node (ref "C123") (pin "2") (pinfunction "2_2") (pintype "passive"))
      (node (ref "C125") (pin "2") (pinfunction "2_2") (pintype "passive"))
      (node (ref "C131") (pin "2") (pinfunction "2_2") (pintype "passive"))
      (node (ref "C134") (pin "2") (pinfunction "2_2") (pintype "passive"))
      (node (ref "C143") (pin "2") (pinfunction "2_2") (pintype "passive"))
      (node (ref "C146") (pin "2") (pinfunction "2_2") (pintype "passive"))
      (node (ref "C162") (pin "1") (pinfunction "1_1") (pintype "passive"))
      (node (ref "Q3") (pin "1") (pinfunction "S_1") (pintype "passive"))
      (node (ref "Q3") (pin "2") (pinfunction "S_2") (pintype "passive"))
      (node (ref "Q3") (pin "3") (pinfunction "S_3") (pintype "passive"))
      (node (ref "R152") (pin "2") (pinfunction "2_2") (pintype "passive"))
      (node (ref "TP67") (pin "1") (pinfunction "1_1") (pintype "passive"))
      (node (ref "U19") (pin "12") (pinfunction "BUCK2IN_12") (pintype "passive"))
      (node (ref "U19") (pin "19") (pinfunction "LDO25IN_19") (pintype "passive"))
      (node (ref "U19") (pin "22") (pinfunction "LDO16IN_22") (pintype "passive"))
      (node (ref "U19") (pin "24") (pinfunction "BUCK4IN_24") (pintype "passive"))
      (node (ref "U19") (pin "28") (pinfunction "BUCK3IN_28") (pintype "passive"))
      (node (ref "U19") (pin "36") (pinfunction "VIN_36") (pintype "passive"))
      (node (ref "U19") (pin "8") (pinfunction "BUCK1IN_8") (pintype "passive"))
      (node (ref "U22") (pin "1") (pinfunction "VINA_1") (pintype "passive"))
      (node (ref "U22") (pin "6") (pinfunction "VINSW_6") (pintype "passive"))
      (node (ref "U25") (pin "4") (pinfunction "SOURCE_4") (pintype "passive"))
    )
    (net (code "20") (name "GND") (class "Default")
      (node (ref "B3") (pin "1") (pinfunction "1_1") (pintype "passive"))
      (node (ref "B3") (pin "2") (pinfunction "2_2") (pintype "passive"))
      (node (ref "C100") (pin "1") (pinfunction "1_1") (pintype "passive"))
      (node (ref "C101") (pin "1") (pinfunction "1_1") (pintype "passive"))
      (node (ref "C110") (pin "1") (pinfunction "1_1") (pintype "passive"))
      (node (ref "C113") (pin "1") (pinfunction "1_1") (pintype "passive"))
      (node (ref "C114") (pin "1") (pinfunction "1_1") (pintype "passive"))
      (node (ref "C116") (pin "1") (pinfunction "1_1") (pintype "passive"))
      (node (ref "C120") (pin "1") (pinfunction "1_1") (pintype "passive"))
      (node (ref "C122") (pin "1") (pinfunction "1_1") (pintype "passive"))
      (node (ref "C123") (pin "1") (pinfunction "1_1") (pintype "passive"))
      (node (ref "C125") (pin "1") (pinfunction "1_1") (pintype "passive"))
      (node (ref "C126") (pin "1") (pinfunction "1_1") (pintype "passive"))
      (node (ref "C129") (pin "1") (pinfunction "1_1") (pintype "passive"))
      (node (ref "C131") (pin "1") (pinfunction "1_1") (pintype "passive"))
      (node (ref "C132") (pin "1") (pinfunction "1_1") (pintype "passive"))
      (node (ref "C134") (pin "1") (pinfunction "1_1") (pintype "passive"))
      (node (ref "C141") (pin "1") (pinfunction "1_1") (pintype "passive"))
      (node (ref "C142") (pin "1") (pinfunction "1_1") (pintype "passive"))
      (node (ref "C143") (pin "1") (pinfunction "1_1") (pintype "passive"))
      (node (ref "C144") (pin "1") (pinfunction "1_1") (pintype "passive"))
      (node (ref "C145") (pin "1") (pinfunction "1_1") (pintype "passive"))
      (node (ref "C146") (pin "1") (pinfunction "1_1") (pintype "passive"))
      (node (ref "C151") (pin "1") (pinfunction "1_1") (pintype "passive"))
      (node (ref "C155") (pin "2") (pinfunction "2_2") (pintype "passive"))
      (node (ref "C156") (pin "1") (pinfunction "1_1") (pintype "passive"))
      (node (ref "C160") (pin "2") (pinfunction "2_2") (pintype "passive"))
      (node (ref "C161") (pin "1") (pinfunction "1_1") (pintype "passive"))
      (node (ref "C162") (pin "2") (pinfunction "2_2") (pintype "passive"))
      (node (ref "C166") (pin "1") (pinfunction "1_1") (pintype "passive"))
      (node (ref "C228") (pin "1") (pinfunction "1_1") (pintype "passive"))
      (node (ref "C99") (pin "2") (pinfunction "2_2") (pintype "passive"))
      (node (ref "CN12") (pin "A1") (pinfunction "GND1_A1") (pintype "passive"))
      (node (ref "CN12") (pin "A12") (pinfunction "GND2_A12") (pintype "passive"))
      (node (ref "CN12") (pin "B1") (pinfunction "GND3_B1") (pintype "passive"))
      (node (ref "CN12") (pin "B12") (pinfunction "GND4_B12") (pintype "passive"))
      (node (ref "CN12") (pin "SH1") (pinfunction "Shield1_SH1") (pintype "passive"))
      (node (ref "CN12") (pin "SH2") (pinfunction "Shield2_SH2") (pintype "passive"))
      (node (ref "CN12") (pin "SH3") (pinfunction "Shield3_SH3") (pintype "passive"))
      (node (ref "CN12") (pin "SH4") (pinfunction "Shield4_SH4") (pintype "passive"))
      (node (ref "CN14") (pin "7") (pinfunction "7_7") (pintype "passive"))
      (node (ref "CN14") (pin "8") (pinfunction "8_8") (pintype "passive"))
      (node (ref "LD1") (pin "2") (pintype "passive"))
      (node (ref "R136") (pin "1") (pinfunction "1_1") (pintype "passive"))
      (node (ref "R140") (pin "1") (pinfunction "1_1") (pintype "passive"))
      (node (ref "R145") (pin "1") (pinfunction "1_1") (pintype "passive"))
      (node (ref "R147") (pin "1") (pinfunction "1_1") (pintype "passive"))
      (node (ref "R148") (pin "1") (pinfunction "1_1") (pintype "passive"))
      (node (ref "TP76") (pin "1") (pinfunction "1_1") (pintype "passive"))
      (node (ref "U19") (pin "10") (pinfunction "PGND2_10") (pintype "passive"))
      (node (ref "U19") (pin "15") (pinfunction "GNDLDO_15") (pintype "passive"))
      (node (ref "U19") (pin "26") (pinfunction "PGND4_26") (pintype "passive"))
      (node (ref "U19") (pin "30") (pinfunction "PGND3_30") (pintype "passive"))
      (node (ref "U19") (pin "32") (pinfunction "PGND5_32") (pintype "passive"))
      (node (ref "U19") (pin "41") (pinfunction "AGND_41") (pintype "passive"))
      (node (ref "U19") (pin "6") (pinfunction "PGND1_6") (pintype "passive"))
      (node (ref "U19") (pin "ep") (pinfunction "EPGND_ep") (pintype "passive"))
      (node (ref "U22") (pin "4") (pinfunction "GND_4") (pintype "passive"))
      (node (ref "U22") (pin "8") (pinfunction "PGND_8") (pintype "passive"))
      (node (ref "U25") (pin "13") (pinfunction "GND_13") (pintype "passive"))
      (node (ref "U25") (pin "2") (pinfunction "GND_2") (pintype "passive"))
      (node (ref "U34") (pin "2") (pinfunction "GND_2") (pintype "passive"))
    )
    (net (code "21") (name "Net-(C166-Pad2)") (class "Default")
      (node (ref "C166") (pin "2") (pinfunction "2_2") (pintype "passive"))
      (node (ref "R185") (pin "1") (pinfunction "1_1") (pintype "passive"))
    )
    (net (code "22") (name "Net-(CN12-CC1)") (class "Default")
      (node (ref "C156") (pin "2") (pinfunction "2_2") (pintype "passive"))
      (node (ref "CN12") (pin "A5") (pinfunction "CC1_A5") (pintype "passive"))
      (node (ref "TP77") (pin "1") (pinfunction "1_1") (pintype "passive"))
      (node (ref "U25") (pin "7") (pinfunction "CC1c_7") (pintype "passive"))
    )
    (net (code "23") (name "Net-(CN12-CC2)") (class "Default")
      (node (ref "C151") (pin "2") (pinfunction "2_2") (pintype "passive"))
      (node (ref "CN12") (pin "B5") (pinfunction "CC2_B5") (pintype "passive"))
      (node (ref "TP73") (pin "1") (pinfunction "1_1") (pintype "passive"))
      (node (ref "U25") (pin "9") (pinfunction "CC2c_9") (pintype "passive"))
    )
    (net (code "24") (name "Net-(CN12-VBUS1)") (class "Default")
      (node (ref "C161") (pin "2") (pinfunction "2_2") (pintype "passive"))
      (node (ref "CN12") (pin "A4") (pinfunction "VBUS1_A4") (pintype "passive"))
      (node (ref "CN12") (pin "A9") (pinfunction "VBUS2_A9") (pintype "passive"))
      (node (ref "CN12") (pin "B4") (pinfunction "VBUS3_B4") (pintype "passive"))
      (node (ref "CN12") (pin "B9") (pinfunction "VBUS4_B9") (pintype "passive"))
      (node (ref "R151") (pin "1") (pinfunction "1_1") (pintype "passive"))
      (node (ref "TP68") (pin "1") (pinfunction "1_1") (pintype "passive"))
      (node (ref "U34") (pin "1") (pinfunction "IO1_1") (pintype "passive"))
    )
    (net (code "25") (name "Net-(D5-A)") (class "Default")
      (node (ref "C160") (pin "1") (pinfunction "1_1") (pintype "passive"))
      (node (ref "C167") (pin "2") (pinfunction "2_2") (pintype "passive"))
      (node (ref "D5") (pin "1") (pinfunction "A_1") (pintype "passive"))
      (node (ref "Q3") (pin "5") (pinfunction "D_5") (pintype "passive"))
      (node (ref "Q3") (pin "6") (pinfunction "D_6") (pintype "passive"))
      (node (ref "Q3") (pin "7") (pinfunction "D_7") (pintype "passive"))
      (node (ref "Q3") (pin "8") (pinfunction "D_8") (pintype "passive"))
      (node (ref "R150") (pin "2") (pinfunction "2_2") (pintype "passive"))
      (node (ref "R151") (pin "2") (pinfunction "2_2") (pintype "passive"))
      (node (ref "R185") (pin "2") (pinfunction "2_2") (pintype "passive"))
    )
    (net (code "26") (name "Net-(D5-K)") (class "Default")
      (node (ref "C155") (pin "1") (pinfunction "1_1") (pintype "passive"))
      (node (ref "D5") (pin "2") (pinfunction "K_2") (pintype "passive"))
      (node (ref "U25") (pin "8") (pinfunction "IN_GD_8") (pintype "passive"))
    )
    (net (code "27") (name "Net-(LD1-Pad1)") (class "Default")
      (node (ref "LD1") (pin "1") (pintype "passive"))
      (node (ref "R152") (pin "1") (pinfunction "1_1") (pintype "passive"))
    )
    (net (code "28") (name "Net-(Q3-G)") (class "Default")
      (node (ref "C167") (pin "1") (pinfunction "1_1") (pintype "passive"))
      (node (ref "Q3") (pin "4") (pinfunction "G_4") (pintype "passive"))
      (node (ref "U25") (pin "5") (pinfunction "GATE_5") (pintype "passive"))
    )
    (net (code "29") (name "Net-(U19-INTLDO)") (class "Default")
      (node (ref "C99") (pin "1") (pinfunction "1_1") (pintype "passive"))
      (node (ref "U19") (pin "40") (pinfunction "INTLDO_40") (pintype "passive"))
    )
    (net (code "30") (name "Net-(U19-LDO2OUT)") (class "Default")
      (node (ref "C142") (pin "2") (pinfunction "2_2") (pintype "passive"))
      (node (ref "TP70") (pin "1") (pinfunction "1_1") (pintype "passive"))
      (node (ref "U19") (pin "18") (pinfunction "LDO2OUT_18") (pintype "passive"))
    )
    (net (code "31") (name "Net-(U19-LDO3IN)") (class "Default")
      (node (ref "R140") (pin "2") (pinfunction "2_2") (pintype "passive"))
      (node (ref "U19") (pin "13") (pinfunction "LDO3IN_13") (pintype "passive"))
    )
    (net (code "32") (name "Net-(U19-PONKEYn)") (class "Default")
      (node (ref "B3") (pin "3") (pinfunction "3_3") (pintype "passive"))
      (node (ref "B3") (pin "4") (pinfunction "4_4") (pintype "passive"))
      (node (ref "C228") (pin "2") (pinfunction "2_2") (pintype "passive"))
      (node (ref "U19") (pin "17") (pinfunction "PONKEYn_17") (pintype "passive"))
    )
    (net (code "33") (name "Net-(U19-RSTn)") (class "Default")
      (node (ref "R114") (pin "2") (pinfunction "2_2") (pintype "passive"))
      (node (ref "U19") (pin "1") (pinfunction "RSTn_1") (pintype "passive"))
    )
    (net (code "34") (name "Net-(U19-SWIN)") (class "Default")
      (node (ref "R115") (pin "2") (pinfunction "2_2") (pintype "passive"))
      (node (ref "U19") (pin "37") (pinfunction "SWIN_37") (pintype "passive"))
    )
    (net (code "35") (name "Net-(U19-VLX1)") (class "Default")
      (node (ref "L7") (pin "1") (pinfunction "1_1") (pintype "passive"))
      (node (ref "U19") (pin "7") (pinfunction "VLX1_7") (pintype "passive"))
    )
    (net (code "36") (name "Net-(U19-VLX2)") (class "Default")
      (node (ref "L11") (pin "1") (pinfunction "1_1") (pintype "passive"))
      (node (ref "U19") (pin "11") (pinfunction "VLX2_11") (pintype "passive"))
    )
    (net (code "37") (name "Net-(U19-VLX3)") (class "Default")
      (node (ref "L6") (pin "1") (pinfunction "1_1") (pintype "passive"))
      (node (ref "U19") (pin "29") (pinfunction "VLX3_29") (pintype "passive"))
    )
    (net (code "38") (name "Net-(U19-VLX4)") (class "Default")
      (node (ref "L9") (pin "1") (pinfunction "1_1") (pintype "passive"))
      (node (ref "U19") (pin "25") (pinfunction "VLX4_25") (pintype "passive"))
    )
    (net (code "39") (name "Net-(U22-FB)") (class "Default")
      (node (ref "R135") (pin "1") (pinfunction "1_1") (pintype "passive"))
      (node (ref "R136") (pin "2") (pinfunction "2_2") (pintype "passive"))
      (node (ref "U22") (pin "3") (pinfunction "FB_3") (pintype "passive"))
    )
    (net (code "40") (name "Net-(U22-PG)") (class "Default")
      (node (ref "R186") (pin "1") (pinfunction "1_1") (pintype "passive"))
      (node (ref "U22") (pin "5") (pinfunction "PG_5") (pintype "passive"))
    )
    (net (code "41") (name "Net-(U22-SW)") (class "Default")
      (node (ref "L8") (pin "1") (pinfunction "1_1") (pintype "passive"))
      (node (ref "U22") (pin "7") (pinfunction "SW_7") (pintype "passive"))
    )
    (net (code "42") (name "Net-(U25-VBUS_CTRL)") (class "Default")
      (node (ref "R148") (pin "2") (pinfunction "2_2") (pintype "passive"))
      (node (ref "R150") (pin "1") (pinfunction "1_1") (pintype "passive"))
      (node (ref "U25") (pin "6") (pinfunction "VBUS_CTRL_6") (pintype "passive"))
    )
    (net (code "43") (name "PWR_ON_DB") (class "Default")
      (node (ref "U19") (pin "35") (pinfunction "VBUSOTG_35") (pintype "passive"))
    )
    (net (code "44") (name "VDD") (class "Default")
      (node (ref "C111") (pin "2") (pinfunction "2_2") (pintype "passive"))
      (node (ref "CN14") (pin "13") (pinfunction "13_13") (pintype "passive"))
      (node (ref "R123") (pin "2") (pinfunction "2_2") (pintype "passive"))
      (node (ref "R124") (pin "2") (pinfunction "2_2") (pintype "passive"))
      (node (ref "U19") (pin "31") (pinfunction "VOUT3_31") (pintype "passive"))
      (node (ref "U19") (pin "42") (pinfunction "VIO_42") (pintype "passive"))
      (node (ref "U22") (pin "2") (pinfunction "EN_2") (pintype "passive"))
      (node (ref "U25") (pin "10") (pinfunction "~{DB}_10") (pintype "passive"))
      (node (ref "U25") (pin "12") (pinfunction "VCC_12") (pintype "passive"))
    )
    (net (code "45") (name "VDD_ADC") (class "Default")
      (node (ref "C132") (pin "2") (pinfunction "2_2") (pintype "passive"))
      (node (ref "TP66") (pin "1") (pinfunction "1_1") (pintype "passive"))
      (node (ref "U19") (pin "23") (pinfunction "LDO1OUT_23") (pintype "passive"))
    )
    (net (code "46") (name "VDD_CORE") (class "Default")
      (node (ref "C127") (pin "2") (pinfunction "2_2") (pintype "passive"))
      (node (ref "CN14") (pin "9") (pinfunction "9_9") (pintype "passive"))
      (node (ref "R131") (pin "2") (pinfunction "2_2") (pintype "passive"))
      (node (ref "R132") (pin "2") (pinfunction "2_2") (pintype "passive"))
      (node (ref "U19") (pin "27") (pinfunction "VOUT4_27") (pintype "passive"))
    )
    (net (code "47") (name "VDD_CPU") (class "Default")
      (node (ref "C115") (pin "2") (pinfunction "2_2") (pintype "passive"))
      (node (ref "CN14") (pin "1") (pinfunction "1_1") (pintype "passive"))
      (node (ref "R126") (pin "2") (pinfunction "2_2") (pintype "passive"))
      (node (ref "R127") (pin "2") (pinfunction "2_2") (pintype "passive"))
      (node (ref "U19") (pin "5") (pinfunction "VOUT1_5") (pintype "passive"))
    )
    (net (code "48") (name "VDD_DDR") (class "Default")
      (node (ref "C128") (pin "2") (pinfunction "2_2") (pintype "passive"))
      (node (ref "CN14") (pin "3") (pinfunction "3_3") (pintype "passive"))
      (node (ref "R137") (pin "2") (pinfunction "2_2") (pintype "passive"))
      (node (ref "R138") (pin "2") (pinfunction "2_2") (pintype "passive"))
      (node (ref "U19") (pin "9") (pinfunction "VOUT2_9") (pintype "passive"))
    )
    (net (code "49") (name "VDD_SD") (class "Default")
      (node (ref "C144") (pin "2") (pinfunction "2_2") (pintype "passive"))
      (node (ref "TP71") (pin "1") (pinfunction "1_1") (pintype "passive"))
      (node (ref "U19") (pin "20") (pinfunction "LDO5OUT_20") (pintype "passive"))
    )
    (net (code "50") (name "VDD_USB") (class "Default")
      (node (ref "CN14") (pin "5") (pinfunction "5_5") (pintype "passive"))
      (node (ref "R113") (pin "2") (pinfunction "2_2") (pintype "passive"))
    )
    (net (code "51") (name "VREF_DDR") (class "Default")
      (node (ref "C141") (pin "2") (pinfunction "2_2") (pintype "passive"))
      (node (ref "TP69") (pin "1") (pinfunction "1_1") (pintype "passive"))
      (node (ref "U19") (pin "16") (pinfunction "VREF_16") (pintype "passive"))
    )
    (net (code "52") (name "unconnected-(CN12-D+1-PadA6)") (class "Default")
      (node (ref "CN12") (pin "A6") (pinfunction "D+1_A6") (pintype "passive+no_connect"))
    )
    (net (code "53") (name "unconnected-(CN12-D+2-PadB6)") (class "Default")
      (node (ref "CN12") (pin "B6") (pinfunction "D+2_B6") (pintype "passive+no_connect"))
    )
    (net (code "54") (name "unconnected-(CN12-D-1-PadA7)") (class "Default")
      (node (ref "CN12") (pin "A7") (pinfunction "D-1_A7") (pintype "passive+no_connect"))
    )
    (net (code "55") (name "unconnected-(CN12-D-2-PadB7)") (class "Default")
      (node (ref "CN12") (pin "B7") (pinfunction "D-2_B7") (pintype "passive+no_connect"))
    )
    (net (code "56") (name "unconnected-(CN12-RX1+-PadB11)") (class "Default")
      (node (ref "CN12") (pin "B11") (pinfunction "RX1+_B11") (pintype "passive+no_connect"))
    )
    (net (code "57") (name "unconnected-(CN12-RX1--PadB10)") (class "Default")
      (node (ref "CN12") (pin "B10") (pinfunction "RX1-_B10") (pintype "passive+no_connect"))
    )
    (net (code "58") (name "unconnected-(CN12-RX2+-PadA11)") (class "Default")
      (node (ref "CN12") (pin "A11") (pinfunction "RX2+_A11") (pintype "passive+no_connect"))
    )
    (net (code "59") (name "unconnected-(CN12-RX2--PadA10)") (class "Default")
      (node (ref "CN12") (pin "A10") (pinfunction "RX2-_A10") (pintype "passive+no_connect"))
    )
    (net (code "60") (name "unconnected-(CN12-SBU1-PadA8)") (class "Default")
      (node (ref "CN12") (pin "A8") (pinfunction "SBU1_A8") (pintype "passive+no_connect"))
    )
    (net (code "61") (name "unconnected-(CN12-SBU2-PadB8)") (class "Default")
      (node (ref "CN12") (pin "B8") (pinfunction "SBU2_B8") (pintype "passive+no_connect"))
    )
    (net (code "62") (name "unconnected-(CN12-TX1+-PadA2)") (class "Default")
      (node (ref "CN12") (pin "A2") (pinfunction "TX1+_A2") (pintype "passive+no_connect"))
    )
    (net (code "63") (name "unconnected-(CN12-TX1--PadA3)") (class "Default")
      (node (ref "CN12") (pin "A3") (pinfunction "TX1-_A3") (pintype "passive+no_connect"))
    )
    (net (code "64") (name "unconnected-(CN12-TX2+-PadB2)") (class "Default")
      (node (ref "CN12") (pin "B2") (pinfunction "TX2+_B2") (pintype "passive+no_connect"))
    )
    (net (code "65") (name "unconnected-(CN12-TX2--PadB3)") (class "Default")
      (node (ref "CN12") (pin "B3") (pinfunction "TX2-_B3") (pintype "passive+no_connect"))
    )
    (net (code "66") (name "unconnected-(CN14-Pad11)") (class "Default")
      (node (ref "CN14") (pin "11") (pinfunction "11_11") (pintype "passive+no_connect"))
    )
    (net (code "67") (name "unconnected-(CN14-Pad12)") (class "Default")
      (node (ref "CN14") (pin "12") (pinfunction "12_12") (pintype "passive+no_connect"))
    )
    (net (code "68") (name "unconnected-(U19-BSTOUT-Pad34)") (class "Default")
      (node (ref "U19") (pin "34") (pinfunction "BSTOUT_34") (pintype "passive+no_connect"))
    )
    (net (code "69") (name "unconnected-(U19-LDO3OUT-Pad14)") (class "Default")
      (node (ref "U19") (pin "14") (pinfunction "LDO3OUT_14") (pintype "passive+no_connect"))
    )
    (net (code "70") (name "unconnected-(U19-VLXBST-Pad33)") (class "Default")
      (node (ref "U19") (pin "33") (pinfunction "VLXBST_33") (pintype "passive+no_connect"))
    )
    (net (code "71") (name "unconnected-(U25-FLT-Pad11)") (class "Default")
      (node (ref "U25") (pin "11") (pinfunction "FLT_11") (pintype "passive+no_connect"))
    )
  )
)
